# P08_eMMC.net
KiCad netlist of a schematic drawn in Altium Designer
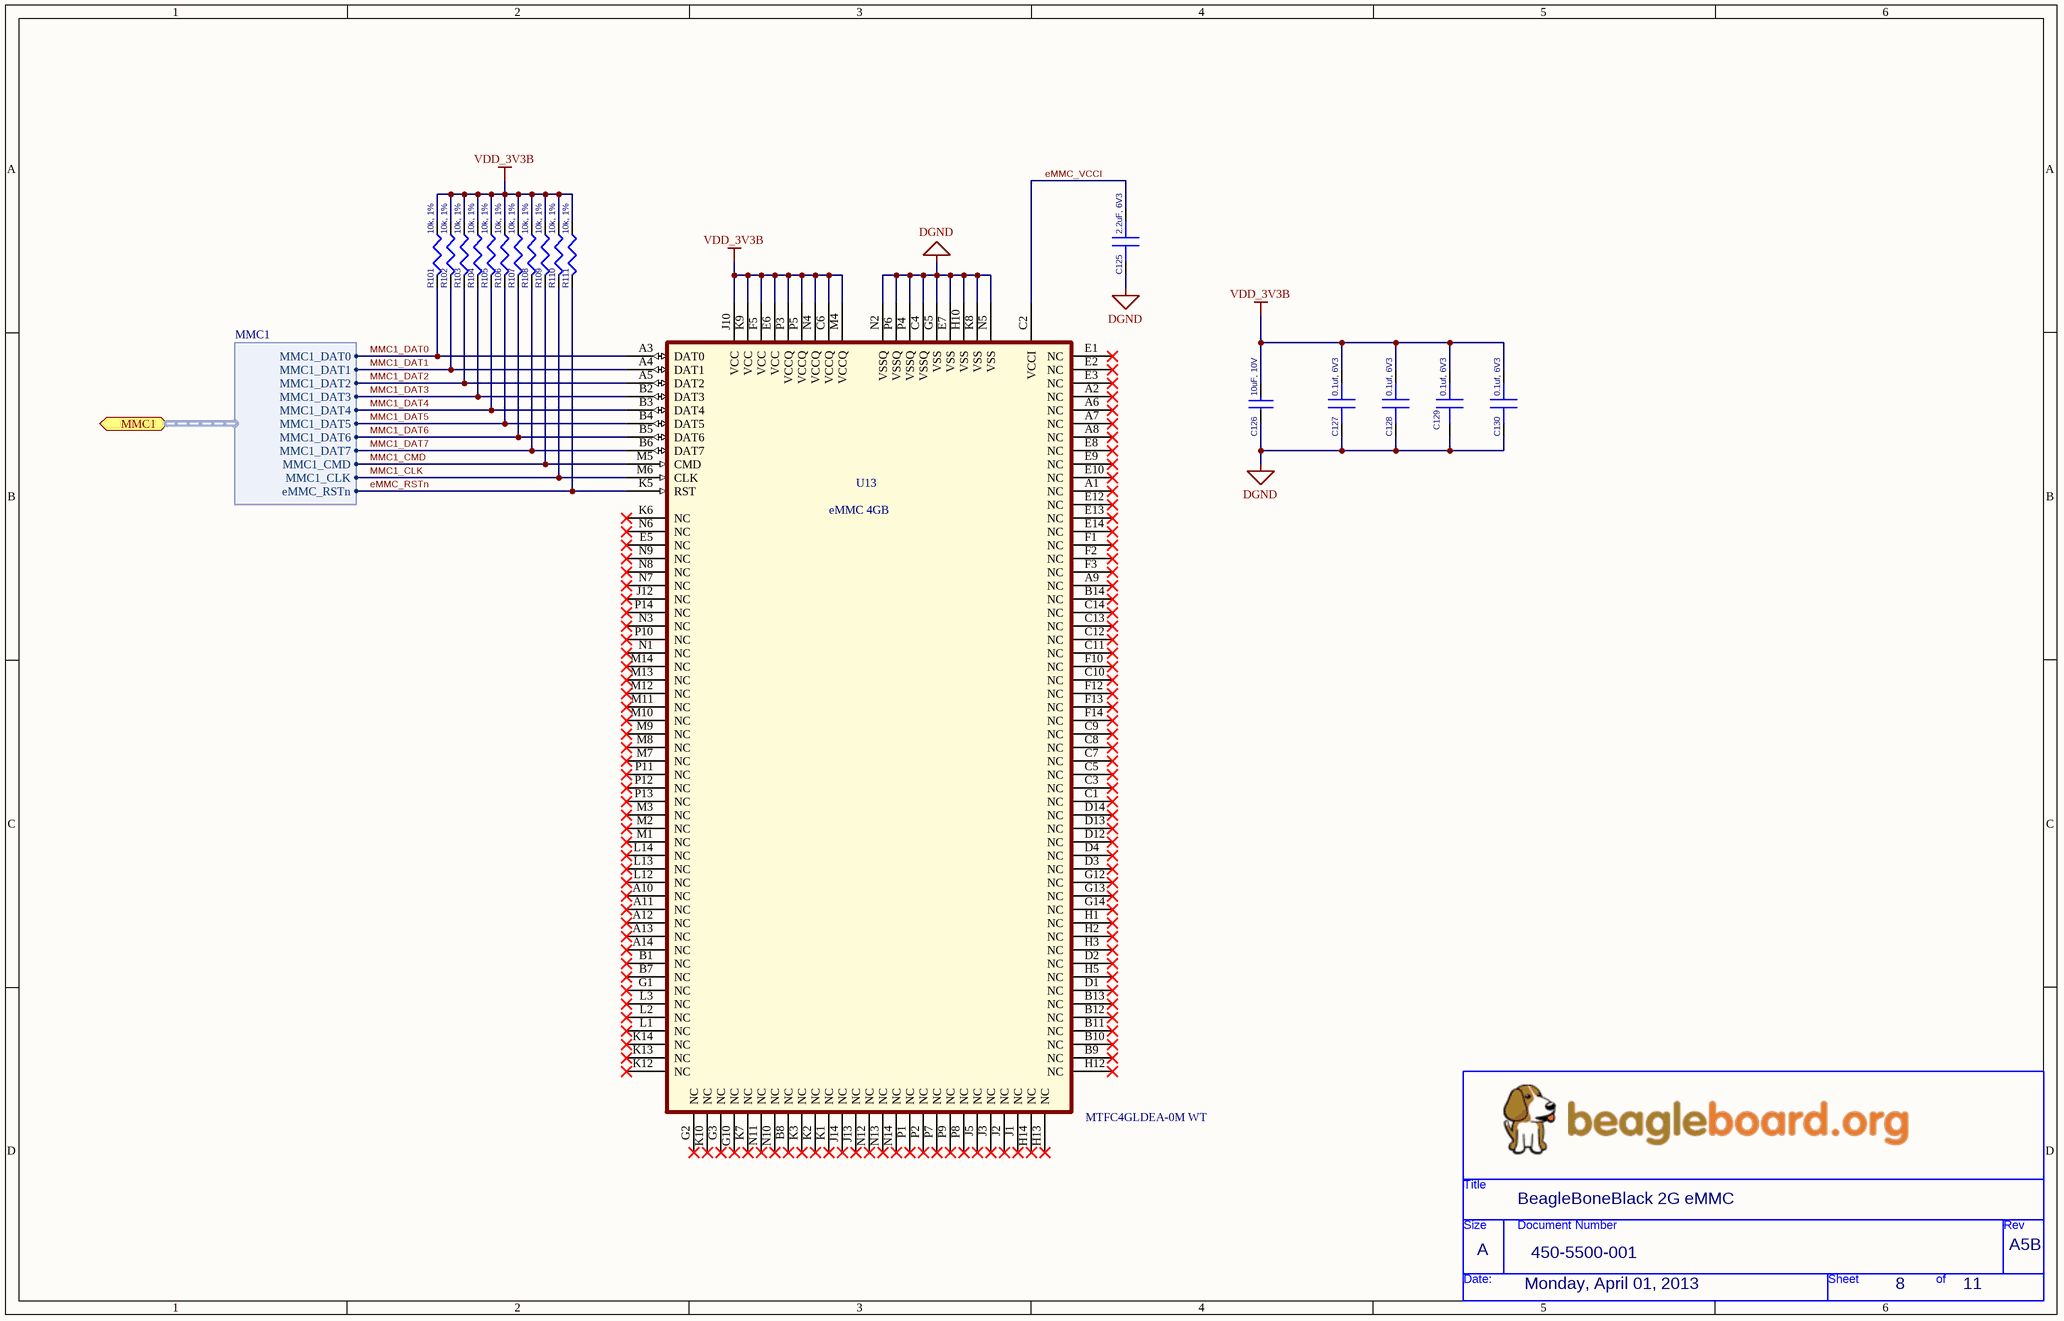
[diagram p0: P08_eMMC.SchDoc]

(export (version "E")
  (design (tool "Eeschema 10.0.6"))
  (components
    (comp (ref "C125")
      (value "2.2uF, 6V3")
      (footprint "402")
      (description "CAP CER 2.2UF 6.3V 10% X5R 0402")
      (fields
        (field (name "MANUFACTURER") "TDK Corporation")
        (field (name "MANUFACTURER PART NUMBER") "C1005X5R0J225K050BC")
      )
      (libsource (lib "BEAGLEBONEBLACK_REV A5B") (part "CAP SMD"))
    )
    (comp (ref "C126")
      (value "10uF, 10V")
      (footprint "805")
      (description "CAP CER 10UF 10V Y5V 0805")
      (fields
        (field (name "MANUFACTURER") "TDK Corporation")
        (field (name "MANUFACTURER PART NUMBER") "C2012Y5V1A106Z")
      )
      (libsource (lib "BEAGLEBONEBLACK_REV A5B") (part "CAP_4.7uF_X5R_6.3V_10%_0603"))
    )
    (comp (ref "C127")
      (value "0.1uf, 6V3")
      (footprint "402")
      (description "CAP CER 0.1UF 6.3V 10% X5R 0402")
      (fields
        (field (name "MANUFACTURER") "TDK Corporation")
        (field (name "MANUFACTURER PART NUMBER") "C1005X5R0J104K050BA")
      )
      (libsource (lib "BEAGLEBONEBLACK_REV A5B") (part "CAP SMD"))
    )
    (comp (ref "C128")
      (value "0.1uf, 6V3")
      (footprint "402")
      (description "CAP CER 0.1UF 6.3V 10% X5R 0402")
      (fields
        (field (name "MANUFACTURER") "TDK Corporation")
        (field (name "MANUFACTURER PART NUMBER") "C1005X5R0J104K050BA")
      )
      (libsource (lib "BEAGLEBONEBLACK_REV A5B") (part "CAP SMD"))
    )
    (comp (ref "C129")
      (value "0.1uf, 6V3")
      (footprint "402")
      (description "CAP CER 0.1UF 6.3V 10% X5R 0402")
      (fields
        (field (name "MANUFACTURER") "TDK Corporation")
        (field (name "MANUFACTURER PART NUMBER") "C1005X5R0J104K050BA")
      )
      (libsource (lib "BEAGLEBONEBLACK_REV A5B") (part "CAP SMD"))
    )
    (comp (ref "C130")
      (value "0.1uf, 6V3")
      (footprint "402")
      (description "CAP CER 0.1UF 6.3V 10% X5R 0402")
      (fields
        (field (name "MANUFACTURER") "TDK Corporation")
        (field (name "MANUFACTURER PART NUMBER") "C1005X5R0J104K050BA")
      )
      (libsource (lib "BEAGLEBONEBLACK_REV A5B") (part "CAP SMD"))
    )
    (comp (ref "R101")
      (value "10k, 1%")
      (footprint "402")
      (description "RES 10K OHM 1/16W 5% 0402 SMD")
      (fields
        (field (name "MANUFACTURER") "Rohm Semiconductor")
        (field (name "MANUFACTURER PART NUMBER") "MCR01MZPJ103")
      )
      (libsource (lib "BEAGLEBONEBLACK_REV A5B") (part "RES_10K_1/16W_1%_0402"))
    )
    (comp (ref "R102")
      (value "10k, 1%")
      (footprint "402")
      (description "RES 10K OHM 1/16W 5% 0402 SMD")
      (fields
        (field (name "MANUFACTURER") "Rohm Semiconductor")
        (field (name "MANUFACTURER PART NUMBER") "MCR01MZPJ103")
      )
      (libsource (lib "BEAGLEBONEBLACK_REV A5B") (part "RES_10K_1/16W_1%_0402"))
    )
    (comp (ref "R103")
      (value "10k, 1%")
      (footprint "402")
      (description "RES 10K OHM 1/16W 5% 0402 SMD")
      (fields
        (field (name "MANUFACTURER") "Rohm Semiconductor")
        (field (name "MANUFACTURER PART NUMBER") "MCR01MZPJ103")
      )
      (libsource (lib "BEAGLEBONEBLACK_REV A5B") (part "RES_10K_1/16W_1%_0402"))
    )
    (comp (ref "R104")
      (value "10k, 1%")
      (footprint "402")
      (description "RES 10K OHM 1/16W 5% 0402 SMD")
      (fields
        (field (name "MANUFACTURER") "Rohm Semiconductor")
        (field (name "MANUFACTURER PART NUMBER") "MCR01MZPJ103")
      )
      (libsource (lib "BEAGLEBONEBLACK_REV A5B") (part "RES_10K_1/16W_1%_0402"))
    )
    (comp (ref "R105")
      (value "10k, 1%")
      (footprint "402")
      (description "RES 10K OHM 1/16W 5% 0402 SMD")
      (fields
        (field (name "MANUFACTURER") "Rohm Semiconductor")
        (field (name "MANUFACTURER PART NUMBER") "MCR01MZPJ103")
      )
      (libsource (lib "BEAGLEBONEBLACK_REV A5B") (part "RES_10K_1/16W_1%_0402"))
    )
    (comp (ref "R106")
      (value "10k, 1%")
      (footprint "402")
      (description "RES 10K OHM 1/16W 5% 0402 SMD")
      (fields
        (field (name "MANUFACTURER") "Rohm Semiconductor")
        (field (name "MANUFACTURER PART NUMBER") "MCR01MZPJ103")
      )
      (libsource (lib "BEAGLEBONEBLACK_REV A5B") (part "RES_10K_1/16W_1%_0402"))
    )
    (comp (ref "R107")
      (value "10k, 1%")
      (footprint "402")
      (description "RES 10K OHM 1/16W 5% 0402 SMD")
      (fields
        (field (name "MANUFACTURER") "Rohm Semiconductor")
        (field (name "MANUFACTURER PART NUMBER") "MCR01MZPJ103")
      )
      (libsource (lib "BEAGLEBONEBLACK_REV A5B") (part "RES_10K_1/16W_1%_0402"))
    )
    (comp (ref "R108")
      (value "10k, 1%")
      (footprint "402")
      (description "RES 10K OHM 1/16W 5% 0402 SMD")
      (fields
        (field (name "MANUFACTURER") "Rohm Semiconductor")
        (field (name "MANUFACTURER PART NUMBER") "MCR01MZPJ103")
      )
      (libsource (lib "BEAGLEBONEBLACK_REV A5B") (part "RES_10K_1/16W_1%_0402"))
    )
    (comp (ref "R109")
      (value "10k, 1%")
      (footprint "402")
      (description "RES 10K OHM 1/16W 5% 0402 SMD")
      (fields
        (field (name "MANUFACTURER") "Rohm Semiconductor")
        (field (name "MANUFACTURER PART NUMBER") "MCR01MZPJ103")
      )
      (libsource (lib "BEAGLEBONEBLACK_REV A5B") (part "RES_10K_1/16W_1%_0402"))
    )
    (comp (ref "R110")
      (value "10k, 1%")
      (footprint "402")
      (description "RES 10K OHM 1/16W 5% 0402 SMD")
      (fields
        (field (name "MANUFACTURER") "Rohm Semiconductor")
        (field (name "MANUFACTURER PART NUMBER") "MCR01MZPJ103")
      )
      (libsource (lib "BEAGLEBONEBLACK_REV A5B") (part "RES_10K_1/16W_1%_0402"))
    )
    (comp (ref "R111")
      (value "10k, 1%")
      (footprint "402")
      (description "RES 10K OHM 1/16W 5% 0402 SMD")
      (fields
        (field (name "MANUFACTURER") "Rohm Semiconductor")
        (field (name "MANUFACTURER PART NUMBER") "MCR01MZPJ103")
      )
      (libsource (lib "BEAGLEBONEBLACK_REV A5B") (part "RES_10K_1/16W_1%_0402"))
    )
    (comp (ref "U13")
      (value "eMMC 4GB")
      (footprint "BGA153_P14_P5_11P5X13")
      (description "IC FLASH 32G MMC 153WFBGA")
      (fields
        (field (name "MANUFACTURER") "Micron Technology")
        (field (name "MANUFACTURER PART NUMBER") "MTFC4GLDEA-0M WT")
      )
      (libsource (lib "BEAGLEBONEBLACK_REV A5B") (part "eMMC"))
    )
  )
  (nets
    (net (code "2") (name "/MMC1_CLK") (class "Default")
      (node (ref "R110") (pin "2") (pinfunction "2_2") (pintype "passive"))
      (node (ref "U13") (pin "M6") (pinfunction "CLK_M6") (pintype "input"))
    )
    (net (code "3") (name "/MMC1_CMD") (class "Default")
      (node (ref "R109") (pin "2") (pinfunction "2_2") (pintype "passive"))
      (node (ref "U13") (pin "M5") (pinfunction "CMD_M5") (pintype "input"))
    )
    (net (code "4") (name "/MMC1_DAT0") (class "Default")
      (node (ref "R101") (pin "2") (pinfunction "2_2") (pintype "passive"))
      (node (ref "U13") (pin "A3") (pinfunction "DAT0_A3") (pintype "bidirectional"))
    )
    (net (code "5") (name "/MMC1_DAT1") (class "Default")
      (node (ref "R102") (pin "2") (pinfunction "2_2") (pintype "passive"))
      (node (ref "U13") (pin "A4") (pinfunction "DAT1_A4") (pintype "bidirectional"))
    )
    (net (code "6") (name "/MMC1_DAT2") (class "Default")
      (node (ref "R103") (pin "2") (pinfunction "2_2") (pintype "passive"))
      (node (ref "U13") (pin "A5") (pinfunction "DAT2_A5") (pintype "bidirectional"))
    )
    (net (code "7") (name "/MMC1_DAT3") (class "Default")
      (node (ref "R104") (pin "2") (pinfunction "2_2") (pintype "passive"))
      (node (ref "U13") (pin "B2") (pinfunction "DAT3_B2") (pintype "bidirectional"))
    )
    (net (code "8") (name "/MMC1_DAT4") (class "Default")
      (node (ref "R105") (pin "2") (pinfunction "2_2") (pintype "passive"))
      (node (ref "U13") (pin "B3") (pinfunction "DAT4_B3") (pintype "bidirectional"))
    )
    (net (code "9") (name "/MMC1_DAT5") (class "Default")
      (node (ref "R106") (pin "2") (pinfunction "2_2") (pintype "passive"))
      (node (ref "U13") (pin "B4") (pinfunction "DAT5_B4") (pintype "bidirectional"))
    )
    (net (code "10") (name "/MMC1_DAT6") (class "Default")
      (node (ref "R107") (pin "2") (pinfunction "2_2") (pintype "passive"))
      (node (ref "U13") (pin "B5") (pinfunction "DAT6_B5") (pintype "bidirectional"))
    )
    (net (code "11") (name "/MMC1_DAT7") (class "Default")
      (node (ref "R108") (pin "2") (pinfunction "2_2") (pintype "passive"))
      (node (ref "U13") (pin "B6") (pinfunction "DAT7_B6") (pintype "bidirectional"))
    )
    (net (code "12") (name "/eMMC_RSTn") (class "Default")
      (node (ref "R111") (pin "2") (pinfunction "2_2") (pintype "passive"))
      (node (ref "U13") (pin "K5") (pinfunction "RST_K5") (pintype "input"))
    )
    (net (code "13") (name "/eMMC_VCCI") (class "Default")
      (node (ref "C125") (pin "1") (pinfunction "1_1") (pintype "passive"))
      (node (ref "U13") (pin "C2") (pinfunction "VCCI_C2") (pintype "power_in"))
    )
    (net (code "15") (name "DGND") (class "Default")
      (node (ref "C125") (pin "2") (pinfunction "2_2") (pintype "passive"))
      (node (ref "C126") (pin "1") (pinfunction "1_1") (pintype "passive"))
      (node (ref "C127") (pin "2") (pinfunction "2_2") (pintype "passive"))
      (node (ref "C128") (pin "2") (pinfunction "2_2") (pintype "passive"))
      (node (ref "C129") (pin "2") (pinfunction "2_2") (pintype "passive"))
      (node (ref "C130") (pin "2") (pinfunction "2_2") (pintype "passive"))
      (node (ref "U13") (pin "C4") (pinfunction "VSSQ_C4") (pintype "power_in"))
      (node (ref "U13") (pin "E7") (pinfunction "VSS_E7") (pintype "power_in"))
      (node (ref "U13") (pin "G5") (pinfunction "VSS_G5") (pintype "power_in"))
      (node (ref "U13") (pin "H10") (pinfunction "VSS_H10") (pintype "power_in"))
      (node (ref "U13") (pin "K8") (pinfunction "VSS_K8") (pintype "power_in"))
      (node (ref "U13") (pin "N2") (pinfunction "VSSQ_N2") (pintype "power_in"))
      (node (ref "U13") (pin "N5") (pinfunction "VSS_N5") (pintype "power_in"))
      (node (ref "U13") (pin "P4") (pinfunction "VSSQ_P4") (pintype "power_in"))
      (node (ref "U13") (pin "P6") (pinfunction "VSSQ_P6") (pintype "power_in"))
    )
    (net (code "16") (name "VDD_3V3B") (class "Default")
      (node (ref "C126") (pin "2") (pinfunction "2_2") (pintype "passive"))
      (node (ref "C127") (pin "1") (pinfunction "1_1") (pintype "passive"))
      (node (ref "C128") (pin "1") (pinfunction "1_1") (pintype "passive"))
      (node (ref "C129") (pin "1") (pinfunction "1_1") (pintype "passive"))
      (node (ref "C130") (pin "1") (pinfunction "1_1") (pintype "passive"))
      (node (ref "R101") (pin "1") (pinfunction "1_1") (pintype "passive"))
      (node (ref "R102") (pin "1") (pinfunction "1_1") (pintype "passive"))
      (node (ref "R103") (pin "1") (pinfunction "1_1") (pintype "passive"))
      (node (ref "R104") (pin "1") (pinfunction "1_1") (pintype "passive"))
      (node (ref "R105") (pin "1") (pinfunction "1_1") (pintype "passive"))
      (node (ref "R106") (pin "1") (pinfunction "1_1") (pintype "passive"))
      (node (ref "R107") (pin "1") (pinfunction "1_1") (pintype "passive"))
      (node (ref "R108") (pin "1") (pinfunction "1_1") (pintype "passive"))
      (node (ref "R109") (pin "1") (pinfunction "1_1") (pintype "passive"))
      (node (ref "R110") (pin "1") (pinfunction "1_1") (pintype "passive"))
      (node (ref "R111") (pin "1") (pinfunction "1_1") (pintype "passive"))
      (node (ref "U13") (pin "C6") (pinfunction "VCCQ_C6") (pintype "power_in"))
      (node (ref "U13") (pin "E6") (pinfunction "VCC_E6") (pintype "power_in"))
      (node (ref "U13") (pin "F5") (pinfunction "VCC_F5") (pintype "power_in"))
      (node (ref "U13") (pin "J10") (pinfunction "VCC_J10") (pintype "power_in"))
      (node (ref "U13") (pin "K9") (pinfunction "VCC_K9") (pintype "power_in"))
      (node (ref "U13") (pin "M4") (pinfunction "VCCQ_M4") (pintype "power_in"))
      (node (ref "U13") (pin "N4") (pinfunction "VCCQ_N4") (pintype "power_in"))
      (node (ref "U13") (pin "P3") (pinfunction "VCCQ_P3") (pintype "power_in"))
      (node (ref "U13") (pin "P5") (pinfunction "VCCQ_P5") (pintype "power_in"))
    )
    (net (code "17") (name "unconnected-(U13-NC-PadA1)") (class "Default")
      (node (ref "U13") (pin "A1") (pinfunction "NC_A1") (pintype "passive+no_connect"))
    )
    (net (code "18") (name "unconnected-(U13-NC-PadA2)") (class "Default")
      (node (ref "U13") (pin "A2") (pinfunction "NC_A2") (pintype "passive+no_connect"))
    )
    (net (code "19") (name "unconnected-(U13-NC-PadA6)") (class "Default")
      (node (ref "U13") (pin "A6") (pinfunction "NC_A6") (pintype "passive+no_connect"))
    )
    (net (code "20") (name "unconnected-(U13-NC-PadA7)") (class "Default")
      (node (ref "U13") (pin "A7") (pinfunction "NC_A7") (pintype "passive+no_connect"))
    )
    (net (code "21") (name "unconnected-(U13-NC-PadA8)") (class "Default")
      (node (ref "U13") (pin "A8") (pinfunction "NC_A8") (pintype "passive+no_connect"))
    )
    (net (code "22") (name "unconnected-(U13-NC-PadA9)") (class "Default")
      (node (ref "U13") (pin "A9") (pinfunction "NC_A9") (pintype "passive+no_connect"))
    )
    (net (code "23") (name "unconnected-(U13-NC-PadA10)") (class "Default")
      (node (ref "U13") (pin "A10") (pinfunction "NC_A10") (pintype "passive+no_connect"))
    )
    (net (code "24") (name "unconnected-(U13-NC-PadA11)") (class "Default")
      (node (ref "U13") (pin "A11") (pinfunction "NC_A11") (pintype "passive+no_connect"))
    )
    (net (code "25") (name "unconnected-(U13-NC-PadA12)") (class "Default")
      (node (ref "U13") (pin "A12") (pinfunction "NC_A12") (pintype "passive+no_connect"))
    )
    (net (code "26") (name "unconnected-(U13-NC-PadA13)") (class "Default")
      (node (ref "U13") (pin "A13") (pinfunction "NC_A13") (pintype "passive+no_connect"))
    )
    (net (code "27") (name "unconnected-(U13-NC-PadA14)") (class "Default")
      (node (ref "U13") (pin "A14") (pinfunction "NC_A14") (pintype "passive+no_connect"))
    )
    (net (code "28") (name "unconnected-(U13-NC-PadB1)") (class "Default")
      (node (ref "U13") (pin "B1") (pinfunction "NC_B1") (pintype "passive+no_connect"))
    )
    (net (code "29") (name "unconnected-(U13-NC-PadB7)") (class "Default")
      (node (ref "U13") (pin "B7") (pinfunction "NC_B7") (pintype "passive+no_connect"))
    )
    (net (code "30") (name "unconnected-(U13-NC-PadB8)") (class "Default")
      (node (ref "U13") (pin "B8") (pinfunction "NC_B8") (pintype "passive+no_connect"))
    )
    (net (code "31") (name "unconnected-(U13-NC-PadB9)") (class "Default")
      (node (ref "U13") (pin "B9") (pinfunction "NC_B9") (pintype "passive+no_connect"))
    )
    (net (code "32") (name "unconnected-(U13-NC-PadB10)") (class "Default")
      (node (ref "U13") (pin "B10") (pinfunction "NC_B10") (pintype "passive+no_connect"))
    )
    (net (code "33") (name "unconnected-(U13-NC-PadB11)") (class "Default")
      (node (ref "U13") (pin "B11") (pinfunction "NC_B11") (pintype "passive+no_connect"))
    )
    (net (code "34") (name "unconnected-(U13-NC-PadB12)") (class "Default")
      (node (ref "U13") (pin "B12") (pinfunction "NC_B12") (pintype "passive+no_connect"))
    )
    (net (code "35") (name "unconnected-(U13-NC-PadB13)") (class "Default")
      (node (ref "U13") (pin "B13") (pinfunction "NC_B13") (pintype "passive+no_connect"))
    )
    (net (code "36") (name "unconnected-(U13-NC-PadB14)") (class "Default")
      (node (ref "U13") (pin "B14") (pinfunction "NC_B14") (pintype "passive+no_connect"))
    )
    (net (code "37") (name "unconnected-(U13-NC-PadC1)") (class "Default")
      (node (ref "U13") (pin "C1") (pinfunction "NC_C1") (pintype "passive+no_connect"))
    )
    (net (code "38") (name "unconnected-(U13-NC-PadC3)") (class "Default")
      (node (ref "U13") (pin "C3") (pinfunction "NC_C3") (pintype "passive+no_connect"))
    )
    (net (code "39") (name "unconnected-(U13-NC-PadC5)") (class "Default")
      (node (ref "U13") (pin "C5") (pinfunction "NC_C5") (pintype "passive+no_connect"))
    )
    (net (code "40") (name "unconnected-(U13-NC-PadC7)") (class "Default")
      (node (ref "U13") (pin "C7") (pinfunction "NC_C7") (pintype "passive+no_connect"))
    )
    (net (code "41") (name "unconnected-(U13-NC-PadC8)") (class "Default")
      (node (ref "U13") (pin "C8") (pinfunction "NC_C8") (pintype "passive+no_connect"))
    )
    (net (code "42") (name "unconnected-(U13-NC-PadC9)") (class "Default")
      (node (ref "U13") (pin "C9") (pinfunction "NC_C9") (pintype "passive+no_connect"))
    )
    (net (code "43") (name "unconnected-(U13-NC-PadC10)") (class "Default")
      (node (ref "U13") (pin "C10") (pinfunction "NC_C10") (pintype "passive+no_connect"))
    )
    (net (code "44") (name "unconnected-(U13-NC-PadC11)") (class "Default")
      (node (ref "U13") (pin "C11") (pinfunction "NC_C11") (pintype "passive+no_connect"))
    )
    (net (code "45") (name "unconnected-(U13-NC-PadC12)") (class "Default")
      (node (ref "U13") (pin "C12") (pinfunction "NC_C12") (pintype "passive+no_connect"))
    )
    (net (code "46") (name "unconnected-(U13-NC-PadC13)") (class "Default")
      (node (ref "U13") (pin "C13") (pinfunction "NC_C13") (pintype "passive+no_connect"))
    )
    (net (code "47") (name "unconnected-(U13-NC-PadC14)") (class "Default")
      (node (ref "U13") (pin "C14") (pinfunction "NC_C14") (pintype "passive+no_connect"))
    )
    (net (code "48") (name "unconnected-(U13-NC-PadD1)") (class "Default")
      (node (ref "U13") (pin "D1") (pinfunction "NC_D1") (pintype "passive+no_connect"))
    )
    (net (code "49") (name "unconnected-(U13-NC-PadD2)") (class "Default")
      (node (ref "U13") (pin "D2") (pinfunction "NC_D2") (pintype "passive+no_connect"))
    )
    (net (code "50") (name "unconnected-(U13-NC-PadD3)") (class "Default")
      (node (ref "U13") (pin "D3") (pinfunction "NC_D3") (pintype "passive+no_connect"))
    )
    (net (code "51") (name "unconnected-(U13-NC-PadD4)") (class "Default")
      (node (ref "U13") (pin "D4") (pinfunction "NC_D4") (pintype "passive+no_connect"))
    )
    (net (code "52") (name "unconnected-(U13-NC-PadD12)") (class "Default")
      (node (ref "U13") (pin "D12") (pinfunction "NC_D12") (pintype "passive+no_connect"))
    )
    (net (code "53") (name "unconnected-(U13-NC-PadD13)") (class "Default")
      (node (ref "U13") (pin "D13") (pinfunction "NC_D13") (pintype "passive+no_connect"))
    )
    (net (code "54") (name "unconnected-(U13-NC-PadD14)") (class "Default")
      (node (ref "U13") (pin "D14") (pinfunction "NC_D14") (pintype "passive+no_connect"))
    )
    (net (code "55") (name "unconnected-(U13-NC-PadE1)") (class "Default")
      (node (ref "U13") (pin "E1") (pinfunction "NC_E1") (pintype "passive+no_connect"))
    )
    (net (code "56") (name "unconnected-(U13-NC-PadE2)") (class "Default")
      (node (ref "U13") (pin "E2") (pinfunction "NC_E2") (pintype "passive+no_connect"))
    )
    (net (code "57") (name "unconnected-(U13-NC-PadE3)") (class "Default")
      (node (ref "U13") (pin "E3") (pinfunction "NC_E3") (pintype "passive+no_connect"))
    )
    (net (code "58") (name "unconnected-(U13-NC-PadE5)") (class "Default")
      (node (ref "U13") (pin "E5") (pinfunction "NC_E5") (pintype "passive+no_connect"))
    )
    (net (code "59") (name "unconnected-(U13-NC-PadE8)") (class "Default")
      (node (ref "U13") (pin "E8") (pinfunction "NC_E8") (pintype "passive+no_connect"))
    )
    (net (code "60") (name "unconnected-(U13-NC-PadE9)") (class "Default")
      (node (ref "U13") (pin "E9") (pinfunction "NC_E9") (pintype "passive+no_connect"))
    )
    (net (code "61") (name "unconnected-(U13-NC-PadE10)") (class "Default")
      (node (ref "U13") (pin "E10") (pinfunction "NC_E10") (pintype "passive+no_connect"))
    )
    (net (code "62") (name "unconnected-(U13-NC-PadE12)") (class "Default")
      (node (ref "U13") (pin "E12") (pinfunction "NC_E12") (pintype "passive+no_connect"))
    )
    (net (code "63") (name "unconnected-(U13-NC-PadE13)") (class "Default")
      (node (ref "U13") (pin "E13") (pinfunction "NC_E13") (pintype "passive+no_connect"))
    )
    (net (code "64") (name "unconnected-(U13-NC-PadE14)") (class "Default")
      (node (ref "U13") (pin "E14") (pinfunction "NC_E14") (pintype "passive+no_connect"))
    )
    (net (code "65") (name "unconnected-(U13-NC-PadF1)") (class "Default")
      (node (ref "U13") (pin "F1") (pinfunction "NC_F1") (pintype "passive+no_connect"))
    )
    (net (code "66") (name "unconnected-(U13-NC-PadF2)") (class "Default")
      (node (ref "U13") (pin "F2") (pinfunction "NC_F2") (pintype "passive+no_connect"))
    )
    (net (code "67") (name "unconnected-(U13-NC-PadF3)") (class "Default")
      (node (ref "U13") (pin "F3") (pinfunction "NC_F3") (pintype "passive+no_connect"))
    )
    (net (code "68") (name "unconnected-(U13-NC-PadF10)") (class "Default")
      (node (ref "U13") (pin "F10") (pinfunction "NC_F10") (pintype "passive+no_connect"))
    )
    (net (code "69") (name "unconnected-(U13-NC-PadF12)") (class "Default")
      (node (ref "U13") (pin "F12") (pinfunction "NC_F12") (pintype "passive+no_connect"))
    )
    (net (code "70") (name "unconnected-(U13-NC-PadF13)") (class "Default")
      (node (ref "U13") (pin "F13") (pinfunction "NC_F13") (pintype "passive+no_connect"))
    )
    (net (code "71") (name "unconnected-(U13-NC-PadF14)") (class "Default")
      (node (ref "U13") (pin "F14") (pinfunction "NC_F14") (pintype "passive+no_connect"))
    )
    (net (code "72") (name "unconnected-(U13-NC-PadG1)") (class "Default")
      (node (ref "U13") (pin "G1") (pinfunction "NC_G1") (pintype "passive+no_connect"))
    )
    (net (code "73") (name "unconnected-(U13-NC-PadG2)") (class "Default")
      (node (ref "U13") (pin "G2") (pinfunction "NC_G2") (pintype "passive+no_connect"))
    )
    (net (code "74") (name "unconnected-(U13-NC-PadG3)") (class "Default")
      (node (ref "U13") (pin "G3") (pinfunction "NC_G3") (pintype "passive+no_connect"))
    )
    (net (code "75") (name "unconnected-(U13-NC-PadG10)") (class "Default")
      (node (ref "U13") (pin "G10") (pinfunction "NC_G10") (pintype "passive+no_connect"))
    )
    (net (code "76") (name "unconnected-(U13-NC-PadG12)") (class "Default")
      (node (ref "U13") (pin "G12") (pinfunction "NC_G12") (pintype "passive+no_connect"))
    )
    (net (code "77") (name "unconnected-(U13-NC-PadG13)") (class "Default")
      (node (ref "U13") (pin "G13") (pinfunction "NC_G13") (pintype "passive+no_connect"))
    )
    (net (code "78") (name "unconnected-(U13-NC-PadG14)") (class "Default")
      (node (ref "U13") (pin "G14") (pinfunction "NC_G14") (pintype "passive+no_connect"))
    )
    (net (code "79") (name "unconnected-(U13-NC-PadH1)") (class "Default")
      (node (ref "U13") (pin "H1") (pinfunction "NC_H1") (pintype "passive+no_connect"))
    )
    (net (code "80") (name "unconnected-(U13-NC-PadH2)") (class "Default")
      (node (ref "U13") (pin "H2") (pinfunction "NC_H2") (pintype "passive+no_connect"))
    )
    (net (code "81") (name "unconnected-(U13-NC-PadH3)") (class "Default")
      (node (ref "U13") (pin "H3") (pinfunction "NC_H3") (pintype "passive+no_connect"))
    )
    (net (code "82") (name "unconnected-(U13-NC-PadH5)") (class "Default")
      (node (ref "U13") (pin "H5") (pinfunction "NC_H5") (pintype "passive+no_connect"))
    )
    (net (code "83") (name "unconnected-(U13-NC-PadH12)") (class "Default")
      (node (ref "U13") (pin "H12") (pinfunction "NC_H12") (pintype "passive+no_connect"))
    )
    (net (code "84") (name "unconnected-(U13-NC-PadH13)") (class "Default")
      (node (ref "U13") (pin "H13") (pinfunction "NC_H13") (pintype "passive+no_connect"))
    )
    (net (code "85") (name "unconnected-(U13-NC-PadH14)") (class "Default")
      (node (ref "U13") (pin "H14") (pinfunction "NC_H14") (pintype "passive+no_connect"))
    )
    (net (code "86") (name "unconnected-(U13-NC-PadJ1)") (class "Default")
      (node (ref "U13") (pin "J1") (pinfunction "NC_J1") (pintype "passive+no_connect"))
    )
    (net (code "87") (name "unconnected-(U13-NC-PadJ2)") (class "Default")
      (node (ref "U13") (pin "J2") (pinfunction "NC_J2") (pintype "passive+no_connect"))
    )
    (net (code "88") (name "unconnected-(U13-NC-PadJ3)") (class "Default")
      (node (ref "U13") (pin "J3") (pinfunction "NC_J3") (pintype "passive+no_connect"))
    )
    (net (code "89") (name "unconnected-(U13-NC-PadJ5)") (class "Default")
      (node (ref "U13") (pin "J5") (pinfunction "NC_J5") (pintype "passive+no_connect"))
    )
    (net (code "90") (name "unconnected-(U13-NC-PadJ12)") (class "Default")
      (node (ref "U13") (pin "J12") (pinfunction "NC_J12") (pintype "passive+no_connect"))
    )
    (net (code "91") (name "unconnected-(U13-NC-PadJ13)") (class "Default")
      (node (ref "U13") (pin "J13") (pinfunction "NC_J13") (pintype "passive+no_connect"))
    )
    (net (code "92") (name "unconnected-(U13-NC-PadJ14)") (class "Default")
      (node (ref "U13") (pin "J14") (pinfunction "NC_J14") (pintype "passive+no_connect"))
    )
    (net (code "93") (name "unconnected-(U13-NC-PadK1)") (class "Default")
      (node (ref "U13") (pin "K1") (pinfunction "NC_K1") (pintype "passive+no_connect"))
    )
    (net (code "94") (name "unconnected-(U13-NC-PadK2)") (class "Default")
      (node (ref "U13") (pin "K2") (pinfunction "NC_K2") (pintype "passive+no_connect"))
    )
    (net (code "95") (name "unconnected-(U13-NC-PadK3)") (class "Default")
      (node (ref "U13") (pin "K3") (pinfunction "NC_K3") (pintype "passive+no_connect"))
    )
    (net (code "96") (name "unconnected-(U13-NC-PadK6)") (class "Default")
      (node (ref "U13") (pin "K6") (pinfunction "NC_K6") (pintype "passive+no_connect"))
    )
    (net (code "97") (name "unconnected-(U13-NC-PadK7)") (class "Default")
      (node (ref "U13") (pin "K7") (pinfunction "NC_K7") (pintype "passive+no_connect"))
    )
    (net (code "98") (name "unconnected-(U13-NC-PadK10)") (class "Default")
      (node (ref "U13") (pin "K10") (pinfunction "NC_K10") (pintype "passive+no_connect"))
    )
    (net (code "99") (name "unconnected-(U13-NC-PadK12)") (class "Default")
      (node (ref "U13") (pin "K12") (pinfunction "NC_K12") (pintype "passive+no_connect"))
    )
    (net (code "100") (name "unconnected-(U13-NC-PadK13)") (class "Default")
      (node (ref "U13") (pin "K13") (pinfunction "NC_K13") (pintype "passive+no_connect"))
    )
    (net (code "101") (name "unconnected-(U13-NC-PadK14)") (class "Default")
      (node (ref "U13") (pin "K14") (pinfunction "NC_K14") (pintype "passive+no_connect"))
    )
    (net (code "102") (name "unconnected-(U13-NC-PadL1)") (class "Default")
      (node (ref "U13") (pin "L1") (pinfunction "NC_L1") (pintype "passive+no_connect"))
    )
    (net (code "103") (name "unconnected-(U13-NC-PadL2)") (class "Default")
      (node (ref "U13") (pin "L2") (pinfunction "NC_L2") (pintype "passive+no_connect"))
    )
    (net (code "104") (name "unconnected-(U13-NC-PadL3)") (class "Default")
      (node (ref "U13") (pin "L3") (pinfunction "NC_L3") (pintype "passive+no_connect"))
    )
    (net (code "105") (name "unconnected-(U13-NC-PadL12)") (class "Default")
      (node (ref "U13") (pin "L12") (pinfunction "NC_L12") (pintype "passive+no_connect"))
    )
    (net (code "106") (name "unconnected-(U13-NC-PadL13)") (class "Default")
      (node (ref "U13") (pin "L13") (pinfunction "NC_L13") (pintype "passive+no_connect"))
    )
    (net (code "107") (name "unconnected-(U13-NC-PadL14)") (class "Default")
      (node (ref "U13") (pin "L14") (pinfunction "NC_L14") (pintype "passive+no_connect"))
    )
    (net (code "108") (name "unconnected-(U13-NC-PadM1)") (class "Default")
      (node (ref "U13") (pin "M1") (pinfunction "NC_M1") (pintype "passive+no_connect"))
    )
    (net (code "109") (name "unconnected-(U13-NC-PadM2)") (class "Default")
      (node (ref "U13") (pin "M2") (pinfunction "NC_M2") (pintype "passive+no_connect"))
    )
    (net (code "110") (name "unconnected-(U13-NC-PadM3)") (class "Default")
      (node (ref "U13") (pin "M3") (pinfunction "NC_M3") (pintype "passive+no_connect"))
    )
    (net (code "111") (name "unconnected-(U13-NC-PadM7)") (class "Default")
      (node (ref "U13") (pin "M7") (pinfunction "NC_M7") (pintype "passive+no_connect"))
    )
    (net (code "112") (name "unconnected-(U13-NC-PadM8)") (class "Default")
      (node (ref "U13") (pin "M8") (pinfunction "NC_M8") (pintype "passive+no_connect"))
    )
    (net (code "113") (name "unconnected-(U13-NC-PadM9)") (class "Default")
      (node (ref "U13") (pin "M9") (pinfunction "NC_M9") (pintype "passive+no_connect"))
    )
    (net (code "114") (name "unconnected-(U13-NC-PadM10)") (class "Default")
      (node (ref "U13") (pin "M10") (pinfunction "NC_M10") (pintype "passive+no_connect"))
    )
    (net (code "115") (name "unconnected-(U13-NC-PadM11)") (class "Default")
      (node (ref "U13") (pin "M11") (pinfunction "NC_M11") (pintype "passive+no_connect"))
    )
    (net (code "116") (name "unconnected-(U13-NC-PadM12)") (class "Default")
      (node (ref "U13") (pin "M12") (pinfunction "NC_M12") (pintype "passive+no_connect"))
    )
    (net (code "117") (name "unconnected-(U13-NC-PadM13)") (class "Default")
      (node (ref "U13") (pin "M13") (pinfunction "NC_M13") (pintype "passive+no_connect"))
    )
    (net (code "118") (name "unconnected-(U13-NC-PadM14)") (class "Default")
      (node (ref "U13") (pin "M14") (pinfunction "NC_M14") (pintype "passive+no_connect"))
    )
    (net (code "119") (name "unconnected-(U13-NC-PadN1)") (class "Default")
      (node (ref "U13") (pin "N1") (pinfunction "NC_N1") (pintype "passive+no_connect"))
    )
    (net (code "120") (name "unconnected-(U13-NC-PadN3)") (class "Default")
      (node (ref "U13") (pin "N3") (pinfunction "NC_N3") (pintype "passive+no_connect"))
    )
    (net (code "121") (name "unconnected-(U13-NC-PadN6)") (class "Default")
      (node (ref "U13") (pin "N6") (pinfunction "NC_N6") (pintype "passive+no_connect"))
    )
    (net (code "122") (name "unconnected-(U13-NC-PadN7)") (class "Default")
      (node (ref "U13") (pin "N7") (pinfunction "NC_N7") (pintype "passive+no_connect"))
    )
    (net (code "123") (name "unconnected-(U13-NC-PadN8)") (class "Default")
      (node (ref "U13") (pin "N8") (pinfunction "NC_N8") (pintype "passive+no_connect"))
    )
    (net (code "124") (name "unconnected-(U13-NC-PadN9)") (class "Default")
      (node (ref "U13") (pin "N9") (pinfunction "NC_N9") (pintype "passive+no_connect"))
    )
    (net (code "125") (name "unconnected-(U13-NC-PadN10)") (class "Default")
      (node (ref "U13") (pin "N10") (pinfunction "NC_N10") (pintype "passive+no_connect"))
    )
    (net (code "126") (name "unconnected-(U13-NC-PadN11)") (class "Default")
      (node (ref "U13") (pin "N11") (pinfunction "NC_N11") (pintype "passive+no_connect"))
    )
    (net (code "127") (name "unconnected-(U13-NC-PadN12)") (class "Default")
      (node (ref "U13") (pin "N12") (pinfunction "NC_N12") (pintype "passive+no_connect"))
    )
    (net (code "128") (name "unconnected-(U13-NC-PadN13)") (class "Default")
      (node (ref "U13") (pin "N13") (pinfunction "NC_N13") (pintype "passive+no_connect"))
    )
    (net (code "129") (name "unconnected-(U13-NC-PadN14)") (class "Default")
      (node (ref "U13") (pin "N14") (pinfunction "NC_N14") (pintype "passive+no_connect"))
    )
    (net (code "130") (name "unconnected-(U13-NC-PadP1)") (class "Default")
      (node (ref "U13") (pin "P1") (pinfunction "NC_P1") (pintype "passive+no_connect"))
    )
    (net (code "131") (name "unconnected-(U13-NC-PadP2)") (class "Default")
      (node (ref "U13") (pin "P2") (pinfunction "NC_P2") (pintype "passive+no_connect"))
    )
    (net (code "132") (name "unconnected-(U13-NC-PadP7)") (class "Default")
      (node (ref "U13") (pin "P7") (pinfunction "NC_P7") (pintype "passive+no_connect"))
    )
    (net (code "133") (name "unconnected-(U13-NC-PadP8)") (class "Default")
      (node (ref "U13") (pin "P8") (pinfunction "NC_P8") (pintype "passive+no_connect"))
    )
    (net (code "134") (name "unconnected-(U13-NC-PadP9)") (class "Default")
      (node (ref "U13") (pin "P9") (pinfunction "NC_P9") (pintype "passive+no_connect"))
    )
    (net (code "135") (name "unconnected-(U13-NC-PadP10)") (class "Default")
      (node (ref "U13") (pin "P10") (pinfunction "NC_P10") (pintype "passive+no_connect"))
    )
    (net (code "136") (name "unconnected-(U13-NC-PadP11)") (class "Default")
      (node (ref "U13") (pin "P11") (pinfunction "NC_P11") (pintype "passive+no_connect"))
    )
    (net (code "137") (name "unconnected-(U13-NC-PadP12)") (class "Default")
      (node (ref "U13") (pin "P12") (pinfunction "NC_P12") (pintype "passive+no_connect"))
    )
    (net (code "138") (name "unconnected-(U13-NC-PadP13)") (class "Default")
      (node (ref "U13") (pin "P13") (pinfunction "NC_P13") (pintype "passive+no_connect"))
    )
    (net (code "139") (name "unconnected-(U13-NC-PadP14)") (class "Default")
      (node (ref "U13") (pin "P14") (pinfunction "NC_P14") (pintype "passive+no_connect"))
    )
  )
)
